# Peripherals.net
KiCad netlist of a schematic drawn in Altium Designer
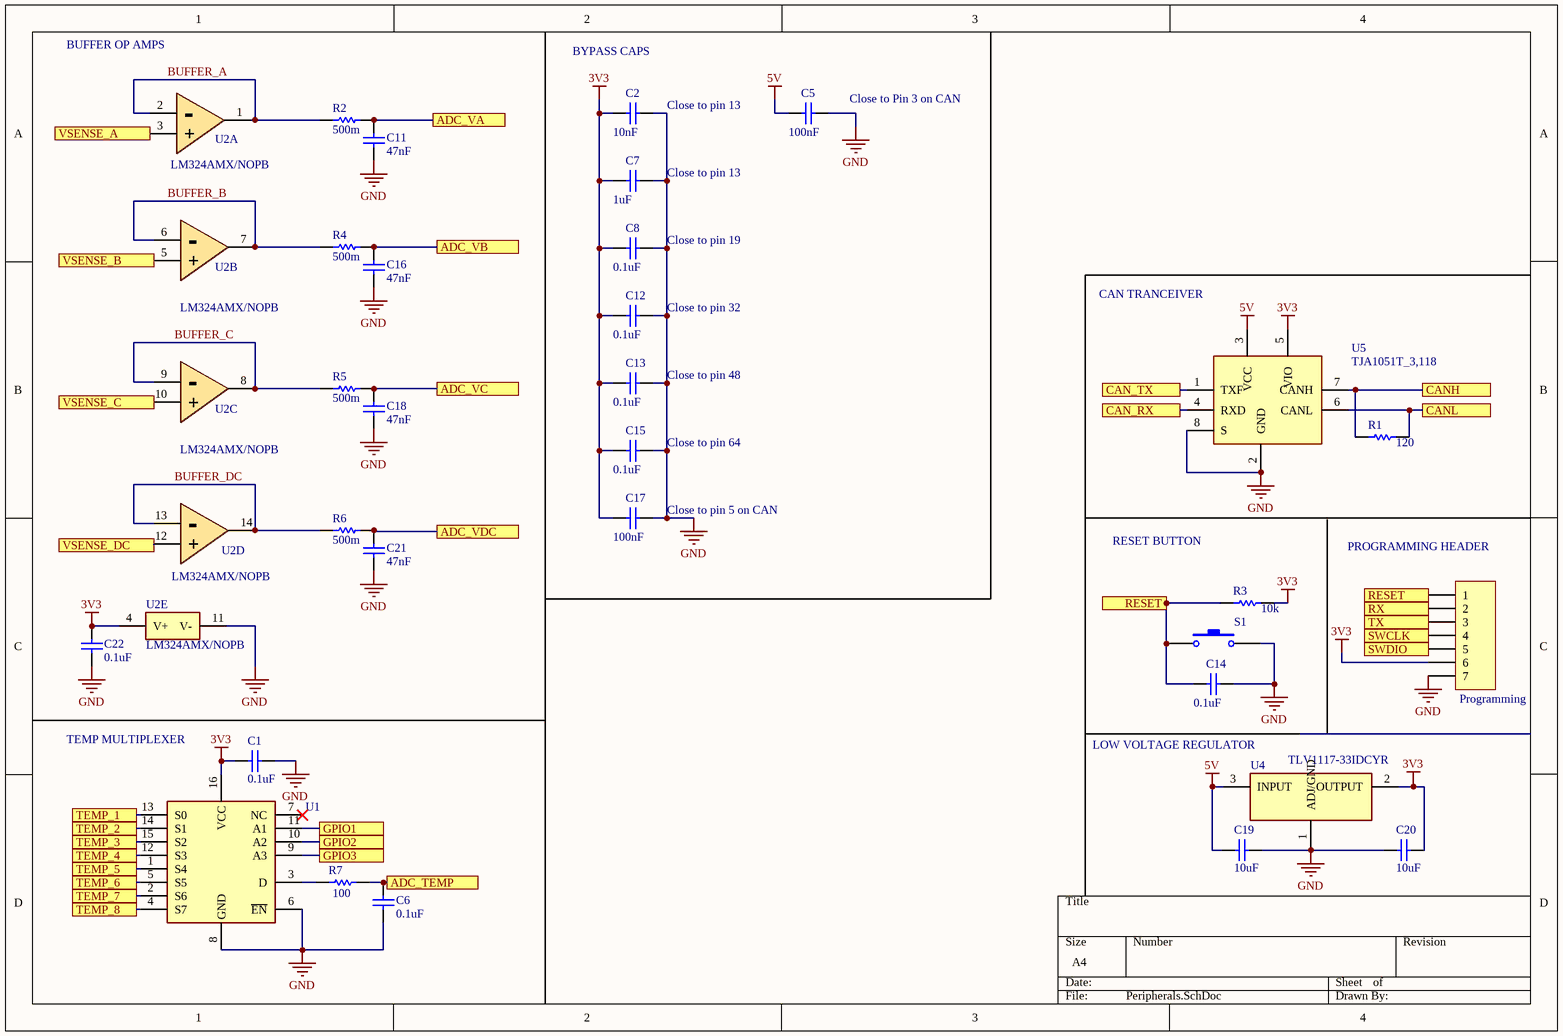
[diagram p0: Peripherals.SchDoc]

(export (version "E")
  (design (tool "Eeschema 10.0.6"))
  (components
    (comp (ref "C1")
      (value "0.1uF")
      (footprint "0805 - Capacitor")
      (description "Nonpolarized Capacitor")
      (fields (field (name "Comment") "Capacitor - Nonpolarized"))
      (libsource (lib "General") (part "Capacitor - Nonpolarized"))
    )
    (comp (ref "C2")
      (value "10nF")
      (footprint "0805 - Capacitor")
      (description "Nonpolarized Capacitor")
      (fields (field (name "Comment") "10V"))
      (libsource (lib "General") (part "Capacitor - Nonpolarized"))
    )
    (comp (ref "C5")
      (value "100nF")
      (footprint "0805 - Capacitor")
      (description "Nonpolarized Capacitor")
      (fields (field (name "Comment") "Capacitor - Nonpolarized"))
      (libsource (lib "General") (part "Capacitor - Nonpolarized"))
    )
    (comp (ref "C6")
      (value "0.1uF")
      (footprint "0805 - Capacitor")
      (description "Nonpolarized Capacitor")
      (fields (field (name "Comment") "Capacitor - Nonpolarized"))
      (libsource (lib "General") (part "Capacitor - Nonpolarized"))
    )
    (comp (ref "C7")
      (value "1uF")
      (footprint "0805 - Capacitor")
      (description "Nonpolarized Capacitor")
      (fields (field (name "Comment") "100V"))
      (libsource (lib "General") (part "Capacitor - Nonpolarized"))
    )
    (comp (ref "C8")
      (value "0.1uF")
      (footprint "0805 - Capacitor")
      (description "Nonpolarized Capacitor")
      (fields (field (name "Comment") "100V"))
      (libsource (lib "General") (part "Capacitor - Nonpolarized"))
    )
    (comp (ref "C11")
      (value "47nF")
      (footprint "0805 - Capacitor")
      (description "Nonpolarized Capacitor")
      (fields (field (name "Comment") "Capacitor - Nonpolarized"))
      (libsource (lib "General") (part "Capacitor - Nonpolarized"))
    )
    (comp (ref "C12")
      (value "0.1uF")
      (footprint "0805 - Capacitor")
      (description "Nonpolarized Capacitor")
      (fields (field (name "Comment") "100V"))
      (libsource (lib "General") (part "Capacitor - Nonpolarized"))
    )
    (comp (ref "C13")
      (value "0.1uF")
      (footprint "0805 - Capacitor")
      (description "Nonpolarized Capacitor")
      (fields (field (name "Comment") "100V"))
      (libsource (lib "General") (part "Capacitor - Nonpolarized"))
    )
    (comp (ref "C14")
      (value "0.1uF")
      (footprint "0805 - Capacitor")
      (description "Nonpolarized Capacitor")
      (fields (field (name "Comment") "100V"))
      (libsource (lib "General") (part "Capacitor - Nonpolarized"))
    )
    (comp (ref "C15")
      (value "0.1uF")
      (footprint "0805 - Capacitor")
      (description "Nonpolarized Capacitor")
      (fields (field (name "Comment") "100V"))
      (libsource (lib "General") (part "Capacitor - Nonpolarized"))
    )
    (comp (ref "C16")
      (value "47nF")
      (footprint "0805 - Capacitor")
      (description "Nonpolarized Capacitor")
      (fields (field (name "Comment") "Capacitor - Nonpolarized"))
      (libsource (lib "General") (part "Capacitor - Nonpolarized"))
    )
    (comp (ref "C17")
      (value "100nF")
      (footprint "0805 - Capacitor")
      (description "Nonpolarized Capacitor")
      (fields (field (name "Comment") "Capacitor - Nonpolarized"))
      (libsource (lib "General") (part "Capacitor - Nonpolarized"))
    )
    (comp (ref "C18")
      (value "47nF")
      (footprint "0805 - Capacitor")
      (description "Nonpolarized Capacitor")
      (fields (field (name "Comment") "Capacitor - Nonpolarized"))
      (libsource (lib "General") (part "Capacitor - Nonpolarized"))
    )
    (comp (ref "C19")
      (value "10uF")
      (footprint "0805 - Capacitor")
      (description "Nonpolarized Capacitor")
      (fields (field (name "Comment") "Capacitor - Nonpolarized"))
      (libsource (lib "General") (part "Capacitor - Nonpolarized"))
    )
    (comp (ref "C20")
      (value "10uF")
      (footprint "0805 - Capacitor")
      (description "Nonpolarized Capacitor")
      (fields (field (name "Comment") "Capacitor - Nonpolarized"))
      (libsource (lib "General") (part "Capacitor - Nonpolarized"))
    )
    (comp (ref "C21")
      (value "47nF")
      (footprint "0805 - Capacitor")
      (description "Nonpolarized Capacitor")
      (fields (field (name "Comment") "Capacitor - Nonpolarized"))
      (libsource (lib "General") (part "Capacitor - Nonpolarized"))
    )
    (comp (ref "C22")
      (value "0.1uF")
      (footprint "0805 - Capacitor")
      (description "Nonpolarized Capacitor")
      (fields (field (name "Comment") "Capacitor - Nonpolarized"))
      (libsource (lib "General") (part "Capacitor - Nonpolarized"))
    )
    (comp (ref "Programming")
      (value "Programming")
      (footprint "HDR1X7")
      (description "1x7 Pin Header")
      (libsource (lib "GeneralConnectors") (part "1x7 Header"))
    )
    (comp (ref "R1")
      (value "120")
      (footprint "0603 - Resistor")
      (description "Resistor")
      (fields (field (name "Comment") "10k"))
      (libsource (lib "General") (part "Resistor"))
    )
    (comp (ref "R2")
      (value "500m")
      (footprint "0603 - Resistor")
      (description "Resistor")
      (libsource (lib "General") (part "Resistor"))
    )
    (comp (ref "R3")
      (value "10k")
      (footprint "0603 - Resistor")
      (description "Resistor")
      (libsource (lib "General") (part "Resistor"))
    )
    (comp (ref "R4")
      (value "500m")
      (footprint "0603 - Resistor")
      (description "Resistor")
      (libsource (lib "General") (part "Resistor"))
    )
    (comp (ref "R5")
      (value "500m")
      (footprint "0603 - Resistor")
      (description "Resistor")
      (libsource (lib "General") (part "Resistor"))
    )
    (comp (ref "R6")
      (value "500m")
      (footprint "0603 - Resistor")
      (description "Resistor")
      (libsource (lib "General") (part "Resistor"))
    )
    (comp (ref "R7")
      (value "100")
      (footprint "0603 - Resistor")
      (description "Resistor")
      (libsource (lib "General") (part "Resistor"))
    )
    (comp (ref "S1")
      (value "Switch - Push Button")
      (footprint "6x6mm Switch")
      (description "Push Button Switch")
      (libsource (lib "General") (part "Switch - Push Button"))
    )
    (comp (ref "U1")
      (value "NX3L4051PW,118")
      (footprint "SOP65P640X120-16N")
      (description "8:1 MUX")
      (fields (field (name "MANUFACTURER") "NXP"))
      (libsource (lib "MC") (part "NX3L4051PW,118"))
    )
    (comp (ref "U2")
      (value "LM324AMX/NOPB")
      (footprint "LM324AMX/NOPB")
      (description "Gen Purp 4Ch Opamp")
      (fields (field (name "MANUFACTURER") "TI"))
      (libsource (lib "GeneralComponents") (part "LM324AMX/NOPB"))
    )
    (comp (ref "U4")
      (value "TLV1117-33IDCYR")
      (footprint "TLV1117")
      (description "Linear Voltage Regulator IC 3.3V 800MA SOT223-4")
      (fields (field (name "MANUFACTURER") "Texas Instruments"))
      (libsource (lib "GeneralComponents") (part "TLV1117-33IDCYR"))
    )
    (comp (ref "U5")
      (value "TJA1051T_3,118")
      (footprint "TJA1051T/3,118")
      (description "CAN Transceiver IC 4.5V-5.5V 250ns")
      (fields (field (name "MANUFACTURER") "NXP") (field (name "MANUFACTURER PART NUMBER") "TJA1051T/3,118"))
      (libsource (lib "GeneralComponents") (part "TJA1051T_3,118"))
    )
  )
  (nets
    (net (code "1") (name "/ADC_TEMP") (class "Default")
      (node (ref "C6") (pin "2") (pinfunction "2_2") (pintype "passive"))
      (node (ref "R7") (pin "1") (pinfunction "1_1") (pintype "passive"))
    )
    (net (code "2") (name "/ADC_VA") (class "Default")
      (node (ref "C11") (pin "2") (pinfunction "2_2") (pintype "passive"))
      (node (ref "R2") (pin "2") (pinfunction "2_2") (pintype "passive"))
    )
    (net (code "3") (name "/ADC_VB") (class "Default")
      (node (ref "C16") (pin "2") (pinfunction "2_2") (pintype "passive"))
      (node (ref "R4") (pin "2") (pinfunction "2_2") (pintype "passive"))
    )
    (net (code "4") (name "/ADC_VC") (class "Default")
      (node (ref "C18") (pin "2") (pinfunction "2_2") (pintype "passive"))
      (node (ref "R5") (pin "2") (pinfunction "2_2") (pintype "passive"))
    )
    (net (code "5") (name "/ADC_VDC") (class "Default")
      (node (ref "C21") (pin "2") (pinfunction "2_2") (pintype "passive"))
      (node (ref "R6") (pin "2") (pinfunction "2_2") (pintype "passive"))
    )
    (net (code "6") (name "/BUFFER_A") (class "Default")
      (node (ref "R2") (pin "1") (pinfunction "1_1") (pintype "passive"))
      (node (ref "U2") (pin "1") (pinfunction "14_1") (pintype "passive"))
      (node (ref "U2") (pin "2") (pinfunction "-_2") (pintype "passive"))
    )
    (net (code "7") (name "/BUFFER_B") (class "Default")
      (node (ref "R4") (pin "1") (pinfunction "1_1") (pintype "passive"))
      (node (ref "U2") (pin "6") (pinfunction "-_6") (pintype "passive"))
      (node (ref "U2") (pin "7") (pinfunction "14_7") (pintype "passive"))
    )
    (net (code "8") (name "/BUFFER_C") (class "Default")
      (node (ref "R5") (pin "1") (pinfunction "1_1") (pintype "passive"))
      (node (ref "U2") (pin "8") (pinfunction "14_8") (pintype "passive"))
      (node (ref "U2") (pin "9") (pinfunction "-_9") (pintype "passive"))
    )
    (net (code "9") (name "/BUFFER_DC") (class "Default")
      (node (ref "R6") (pin "1") (pinfunction "1_1") (pintype "passive"))
      (node (ref "U2") (pin "13") (pinfunction "-_13") (pintype "passive"))
      (node (ref "U2") (pin "14") (pinfunction "14_14") (pintype "passive"))
    )
    (net (code "10") (name "/CANH") (class "Default")
      (node (ref "R1") (pin "2") (pinfunction "2_2") (pintype "passive"))
      (node (ref "U5") (pin "7") (pinfunction "CANH_7") (pintype "passive"))
    )
    (net (code "11") (name "/CANL") (class "Default")
      (node (ref "R1") (pin "1") (pinfunction "1_1") (pintype "passive"))
      (node (ref "U5") (pin "6") (pinfunction "CANL_6") (pintype "passive"))
    )
    (net (code "12") (name "/CAN_RX") (class "Default")
      (node (ref "U5") (pin "4") (pinfunction "RXD_4") (pintype "passive"))
    )
    (net (code "13") (name "/CAN_TX") (class "Default")
      (node (ref "U5") (pin "1") (pinfunction "TXF_1") (pintype "passive"))
    )
    (net (code "14") (name "/GPIO1") (class "Default")
      (node (ref "U1") (pin "11") (pinfunction "A1_11") (pintype "passive"))
    )
    (net (code "15") (name "/GPIO2") (class "Default")
      (node (ref "U1") (pin "10") (pinfunction "A2_10") (pintype "passive"))
    )
    (net (code "16") (name "/GPIO3") (class "Default")
      (node (ref "U1") (pin "9") (pinfunction "A3_9") (pintype "passive"))
    )
    (net (code "17") (name "/RESET") (class "Default")
      (node (ref "C14") (pin "1") (pinfunction "1_1") (pintype "passive"))
      (node (ref "Programming") (pin "1") (pinfunction "1_1") (pintype "passive"))
      (node (ref "R3") (pin "2") (pinfunction "2_2") (pintype "passive"))
      (node (ref "S1") (pin "1") (pinfunction "1_1") (pintype "passive"))
    )
    (net (code "18") (name "/RX") (class "Default")
      (node (ref "Programming") (pin "2") (pinfunction "2_2") (pintype "passive"))
    )
    (net (code "19") (name "/SWCLK") (class "Default")
      (node (ref "Programming") (pin "4") (pinfunction "4_4") (pintype "passive"))
    )
    (net (code "20") (name "/SWDIO") (class "Default")
      (node (ref "Programming") (pin "5") (pinfunction "5_5") (pintype "passive"))
    )
    (net (code "21") (name "/TEMP_1") (class "Default")
      (node (ref "U1") (pin "13") (pinfunction "S0_13") (pintype "passive"))
    )
    (net (code "22") (name "/TEMP_2") (class "Default")
      (node (ref "U1") (pin "14") (pinfunction "S1_14") (pintype "passive"))
    )
    (net (code "23") (name "/TEMP_3") (class "Default")
      (node (ref "U1") (pin "15") (pinfunction "S2_15") (pintype "passive"))
    )
    (net (code "24") (name "/TEMP_4") (class "Default")
      (node (ref "U1") (pin "12") (pinfunction "S3_12") (pintype "passive"))
    )
    (net (code "25") (name "/TEMP_5") (class "Default")
      (node (ref "U1") (pin "1") (pinfunction "S4_1") (pintype "passive"))
    )
    (net (code "26") (name "/TEMP_6") (class "Default")
      (node (ref "U1") (pin "5") (pinfunction "S5_5") (pintype "passive"))
    )
    (net (code "27") (name "/TEMP_7") (class "Default")
      (node (ref "U1") (pin "2") (pinfunction "S6_2") (pintype "passive"))
    )
    (net (code "28") (name "/TEMP_8") (class "Default")
      (node (ref "U1") (pin "4") (pinfunction "S7_4") (pintype "passive"))
    )
    (net (code "29") (name "/TX") (class "Default")
      (node (ref "Programming") (pin "3") (pinfunction "3_3") (pintype "passive"))
    )
    (net (code "30") (name "/VSENSE_A") (class "Default")
      (node (ref "U2") (pin "3") (pinfunction "+_3") (pintype "passive"))
    )
    (net (code "31") (name "/VSENSE_B") (class "Default")
      (node (ref "U2") (pin "5") (pinfunction "+_5") (pintype "passive"))
    )
    (net (code "32") (name "/VSENSE_C") (class "Default")
      (node (ref "U2") (pin "10") (pinfunction "+_10") (pintype "passive"))
    )
    (net (code "33") (name "/VSENSE_DC") (class "Default")
      (node (ref "U2") (pin "12") (pinfunction "+_12") (pintype "passive"))
    )
    (net (code "34") (name "3V3") (class "Default")
      (node (ref "C1") (pin "1") (pinfunction "1_1") (pintype "passive"))
      (node (ref "C12") (pin "1") (pinfunction "1_1") (pintype "passive"))
      (node (ref "C13") (pin "1") (pinfunction "1_1") (pintype "passive"))
      (node (ref "C15") (pin "1") (pinfunction "1_1") (pintype "passive"))
      (node (ref "C17") (pin "2") (pinfunction "2_2") (pintype "passive"))
      (node (ref "C2") (pin "1") (pinfunction "1_1") (pintype "passive"))
      (node (ref "C20") (pin "2") (pinfunction "2_2") (pintype "passive"))
      (node (ref "C22") (pin "1") (pinfunction "1_1") (pintype "passive"))
      (node (ref "C7") (pin "1") (pinfunction "1_1") (pintype "passive"))
      (node (ref "C8") (pin "1") (pinfunction "1_1") (pintype "passive"))
      (node (ref "Programming") (pin "6") (pinfunction "6_6") (pintype "passive"))
      (node (ref "R3") (pin "1") (pinfunction "1_1") (pintype "passive"))
      (node (ref "U1") (pin "16") (pinfunction "VCC_16") (pintype "passive"))
      (node (ref "U2") (pin "4") (pinfunction "V+_4") (pintype "passive"))
      (node (ref "U4") (pin "2") (pinfunction "OUTPUT_2") (pintype "passive"))
      (node (ref "U5") (pin "5") (pinfunction "VIO_5") (pintype "passive"))
    )
    (net (code "35") (name "5V") (class "Default")
      (node (ref "C19") (pin "2") (pinfunction "2_2") (pintype "passive"))
      (node (ref "C5") (pin "2") (pinfunction "2_2") (pintype "passive"))
      (node (ref "U4") (pin "3") (pinfunction "INPUT_3") (pintype "passive"))
      (node (ref "U5") (pin "3") (pinfunction "VCC_3") (pintype "passive"))
    )
    (net (code "36") (name "GND") (class "Default")
      (node (ref "C1") (pin "2") (pinfunction "2_2") (pintype "passive"))
      (node (ref "C11") (pin "1") (pinfunction "1_1") (pintype "passive"))
      (node (ref "C12") (pin "2") (pinfunction "2_2") (pintype "passive"))
      (node (ref "C13") (pin "2") (pinfunction "2_2") (pintype "passive"))
      (node (ref "C14") (pin "2") (pinfunction "2_2") (pintype "passive"))
      (node (ref "C15") (pin "2") (pinfunction "2_2") (pintype "passive"))
      (node (ref "C16") (pin "1") (pinfunction "1_1") (pintype "passive"))
      (node (ref "C17") (pin "1") (pinfunction "1_1") (pintype "passive"))
      (node (ref "C18") (pin "1") (pinfunction "1_1") (pintype "passive"))
      (node (ref "C19") (pin "1") (pinfunction "1_1") (pintype "passive"))
      (node (ref "C2") (pin "2") (pinfunction "2_2") (pintype "passive"))
      (node (ref "C20") (pin "1") (pinfunction "1_1") (pintype "passive"))
      (node (ref "C21") (pin "1") (pinfunction "1_1") (pintype "passive"))
      (node (ref "C22") (pin "2") (pinfunction "2_2") (pintype "passive"))
      (node (ref "C5") (pin "1") (pinfunction "1_1") (pintype "passive"))
      (node (ref "C6") (pin "1") (pinfunction "1_1") (pintype "passive"))
      (node (ref "C7") (pin "2") (pinfunction "2_2") (pintype "passive"))
      (node (ref "C8") (pin "2") (pinfunction "2_2") (pintype "passive"))
      (node (ref "Programming") (pin "7") (pinfunction "7_7") (pintype "passive"))
      (node (ref "S1") (pin "2") (pinfunction "2_2") (pintype "passive"))
      (node (ref "U1") (pin "6") (pinfunction "~{EN}_6") (pintype "passive"))
      (node (ref "U1") (pin "8") (pinfunction "GND_8") (pintype "passive"))
      (node (ref "U2") (pin "11") (pinfunction "V-_11") (pintype "passive"))
      (node (ref "U4") (pin "1") (pinfunction "ADJ/GND_1") (pintype "passive"))
      (node (ref "U5") (pin "2") (pinfunction "GND_2") (pintype "passive"))
      (node (ref "U5") (pin "8") (pinfunction "S_8") (pintype "passive"))
    )
    (net (code "37") (name "Net-(U1-D)") (class "Default")
      (node (ref "R7") (pin "2") (pinfunction "2_2") (pintype "passive"))
      (node (ref "U1") (pin "3") (pinfunction "D_3") (pintype "passive"))
    )
    (net (code "38") (name "unconnected-(U1-NC-Pad7)") (class "Default")
      (node (ref "U1") (pin "7") (pinfunction "NC_7") (pintype "passive+no_connect"))
    )
  )
)
